# H-API_Sequencer.net
KiCad netlist of a schematic drawn in EAGLE
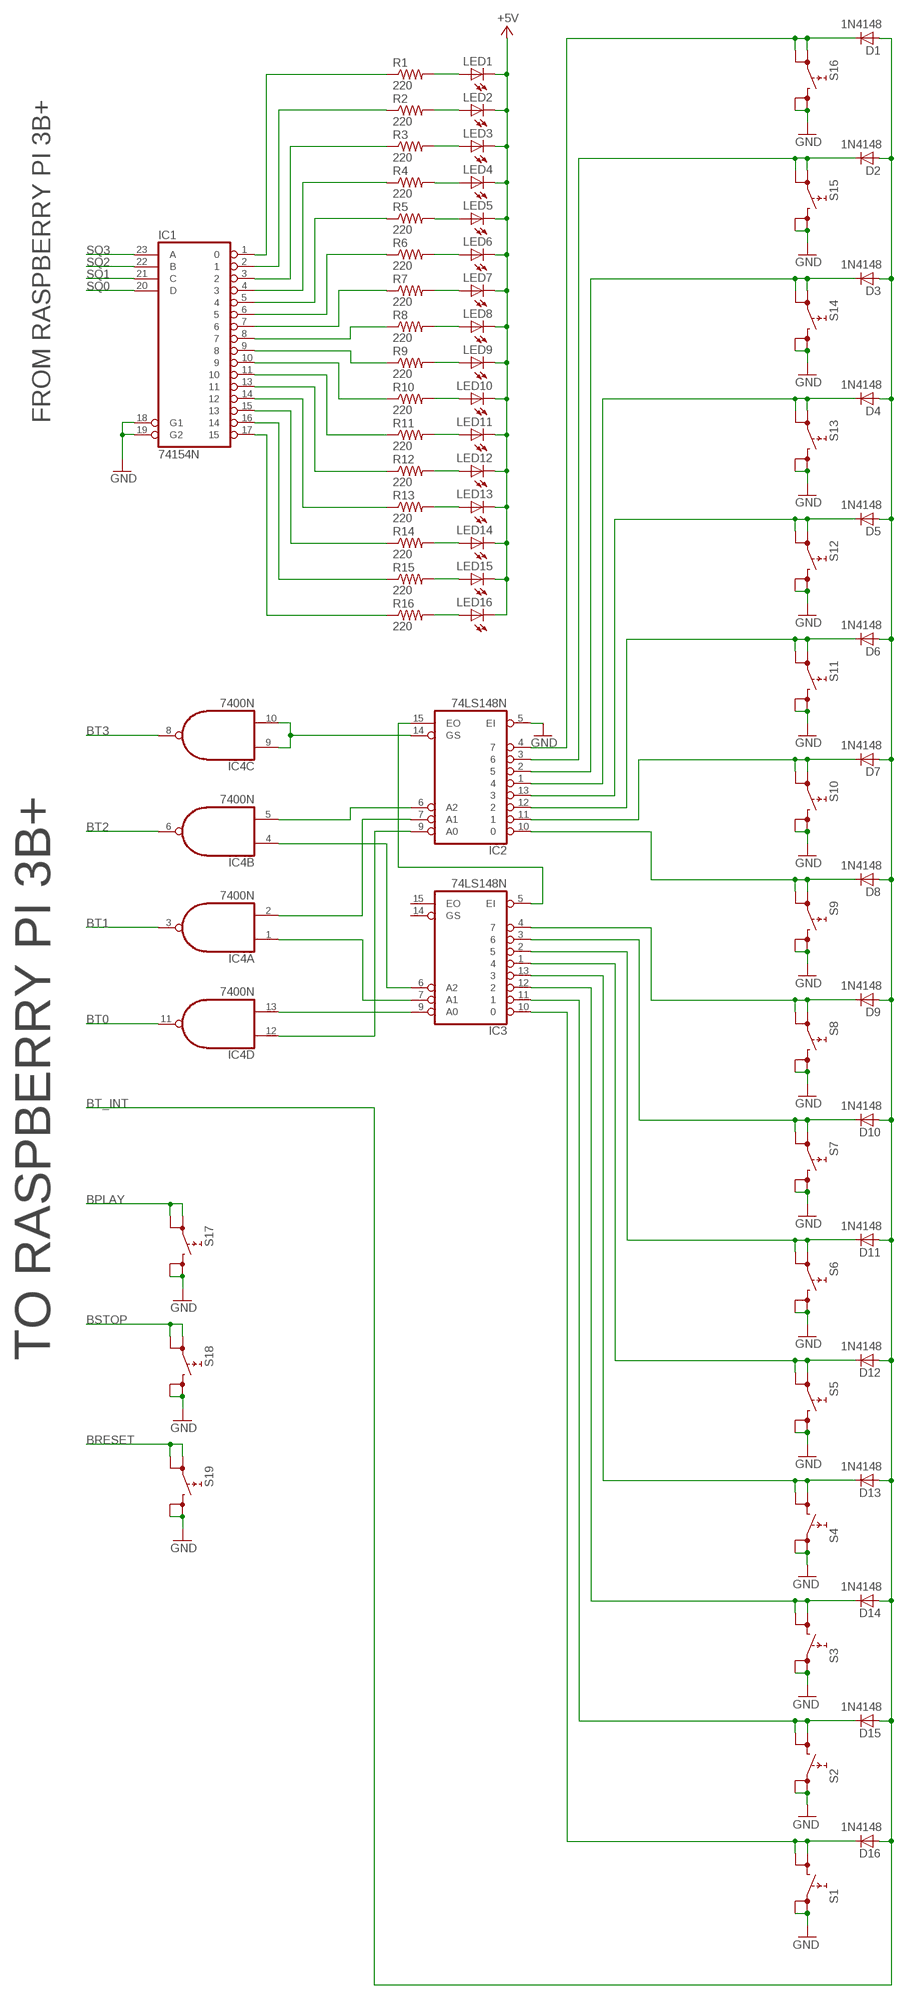
[diagram p0: schematic, sheet 1]

(export (version "E")
  (design (tool "Eeschema 10.0.6"))
  (components
    (comp (ref "IC1")
      (value "74154N")
      (footprint "eagle-import:DIL24-6")
      (libsource (lib "eagle-import") (part "74154N"))
    )
    (comp (ref "IC2")
      (value "74LS148N")
      (footprint "eagle-import:DIL16")
      (libsource (lib "eagle-import") (part "74148NLS"))
    )
    (comp (ref "IC3")
      (value "74LS148N")
      (footprint "eagle-import:DIL16")
      (libsource (lib "eagle-import") (part "74148NLS"))
    )
    (comp (ref "IC4")
      (value "7400N")
      (footprint "eagle-import:DIL14")
      (libsource (lib "eagle-import") (part "7400N"))
    )
    (comp (ref "LED1")
      (value "LED5MM")
      (footprint "eagle-import:LED5MM")
      (libsource (lib "eagle-import") (part "LED5MM"))
    )
    (comp (ref "LED2")
      (value "LED5MM")
      (footprint "eagle-import:LED5MM")
      (libsource (lib "eagle-import") (part "LED5MM"))
    )
    (comp (ref "LED3")
      (value "LED5MM")
      (footprint "eagle-import:LED5MM")
      (libsource (lib "eagle-import") (part "LED5MM"))
    )
    (comp (ref "LED4")
      (value "LED5MM")
      (footprint "eagle-import:LED5MM")
      (libsource (lib "eagle-import") (part "LED5MM"))
    )
    (comp (ref "LED5")
      (value "LED5MM")
      (footprint "eagle-import:LED5MM")
      (libsource (lib "eagle-import") (part "LED5MM"))
    )
    (comp (ref "LED6")
      (value "LED5MM")
      (footprint "eagle-import:LED5MM")
      (libsource (lib "eagle-import") (part "LED5MM"))
    )
    (comp (ref "LED7")
      (value "LED5MM")
      (footprint "eagle-import:LED5MM")
      (libsource (lib "eagle-import") (part "LED5MM"))
    )
    (comp (ref "LED8")
      (value "LED5MM")
      (footprint "eagle-import:LED5MM")
      (libsource (lib "eagle-import") (part "LED5MM"))
    )
    (comp (ref "LED9")
      (value "LED5MM")
      (footprint "eagle-import:LED5MM")
      (libsource (lib "eagle-import") (part "LED5MM"))
    )
    (comp (ref "LED10")
      (value "LED5MM")
      (footprint "eagle-import:LED5MM")
      (libsource (lib "eagle-import") (part "LED5MM"))
    )
    (comp (ref "LED11")
      (value "LED5MM")
      (footprint "eagle-import:LED5MM")
      (libsource (lib "eagle-import") (part "LED5MM"))
    )
    (comp (ref "LED12")
      (value "LED5MM")
      (footprint "eagle-import:LED5MM")
      (libsource (lib "eagle-import") (part "LED5MM"))
    )
    (comp (ref "LED13")
      (value "LED5MM")
      (footprint "eagle-import:LED5MM")
      (libsource (lib "eagle-import") (part "LED5MM"))
    )
    (comp (ref "LED14")
      (value "LED5MM")
      (footprint "eagle-import:LED5MM")
      (libsource (lib "eagle-import") (part "LED5MM"))
    )
    (comp (ref "LED15")
      (value "LED5MM")
      (footprint "eagle-import:LED5MM")
      (libsource (lib "eagle-import") (part "LED5MM"))
    )
    (comp (ref "LED16")
      (value "LED5MM")
      (footprint "eagle-import:LED5MM")
      (libsource (lib "eagle-import") (part "LED5MM"))
    )
    (comp (ref "R1")
      (value "220")
      (footprint "eagle-import:VMTA55")
      (libsource (lib "eagle-import") (part "R-US_VMTA55"))
    )
    (comp (ref "R2")
      (value "220")
      (footprint "eagle-import:VMTA55")
      (libsource (lib "eagle-import") (part "R-US_VMTA55"))
    )
    (comp (ref "R3")
      (value "220")
      (footprint "eagle-import:VMTA55")
      (libsource (lib "eagle-import") (part "R-US_VMTA55"))
    )
    (comp (ref "R4")
      (value "220")
      (footprint "eagle-import:VMTA55")
      (libsource (lib "eagle-import") (part "R-US_VMTA55"))
    )
    (comp (ref "R5")
      (value "220")
      (footprint "eagle-import:VMTA55")
      (libsource (lib "eagle-import") (part "R-US_VMTA55"))
    )
    (comp (ref "R6")
      (value "220")
      (footprint "eagle-import:VMTA55")
      (libsource (lib "eagle-import") (part "R-US_VMTA55"))
    )
    (comp (ref "R7")
      (value "220")
      (footprint "eagle-import:VMTA55")
      (libsource (lib "eagle-import") (part "R-US_VMTA55"))
    )
    (comp (ref "R8")
      (value "220")
      (footprint "eagle-import:VMTA55")
      (libsource (lib "eagle-import") (part "R-US_VMTA55"))
    )
    (comp (ref "R9")
      (value "220")
      (footprint "eagle-import:VMTA55")
      (libsource (lib "eagle-import") (part "R-US_VMTA55"))
    )
    (comp (ref "R10")
      (value "220")
      (footprint "eagle-import:VMTA55")
      (libsource (lib "eagle-import") (part "R-US_VMTA55"))
    )
    (comp (ref "R11")
      (value "220")
      (footprint "eagle-import:VMTA55")
      (libsource (lib "eagle-import") (part "R-US_VMTA55"))
    )
    (comp (ref "R12")
      (value "220")
      (footprint "eagle-import:VMTA55")
      (libsource (lib "eagle-import") (part "R-US_VMTA55"))
    )
    (comp (ref "R13")
      (value "220")
      (footprint "eagle-import:VMTA55")
      (libsource (lib "eagle-import") (part "R-US_VMTA55"))
    )
    (comp (ref "R14")
      (value "220")
      (footprint "eagle-import:VMTA55")
      (libsource (lib "eagle-import") (part "R-US_VMTA55"))
    )
    (comp (ref "R15")
      (value "220")
      (footprint "eagle-import:VMTA55")
      (libsource (lib "eagle-import") (part "R-US_VMTA55"))
    )
    (comp (ref "R16")
      (value "220")
      (footprint "eagle-import:VMTA55")
      (libsource (lib "eagle-import") (part "R-US_VMTA55"))
    )
    (comp (ref "S1")
      (value "REKN")
      (footprint "eagle-import:REKN")
      (libsource (lib "eagle-import") (part "REKN"))
    )
    (comp (ref "S2")
      (value "REKN")
      (footprint "eagle-import:REKN")
      (libsource (lib "eagle-import") (part "REKN"))
    )
    (comp (ref "S3")
      (value "REKN")
      (footprint "eagle-import:REKN")
      (libsource (lib "eagle-import") (part "REKN"))
    )
    (comp (ref "S4")
      (value "REKN")
      (footprint "eagle-import:REKN")
      (libsource (lib "eagle-import") (part "REKN"))
    )
    (comp (ref "S5")
      (value "REKN")
      (footprint "eagle-import:REKN")
      (libsource (lib "eagle-import") (part "REKN"))
    )
    (comp (ref "S6")
      (value "REKN")
      (footprint "eagle-import:REKN")
      (libsource (lib "eagle-import") (part "REKN"))
    )
    (comp (ref "S7")
      (value "REKN")
      (footprint "eagle-import:REKN")
      (libsource (lib "eagle-import") (part "REKN"))
    )
    (comp (ref "S8")
      (value "REKN")
      (footprint "eagle-import:REKN")
      (libsource (lib "eagle-import") (part "REKN"))
    )
    (comp (ref "S9")
      (value "REKN")
      (footprint "eagle-import:REKN")
      (libsource (lib "eagle-import") (part "REKN"))
    )
    (comp (ref "S10")
      (value "REKN")
      (footprint "eagle-import:REKN")
      (libsource (lib "eagle-import") (part "REKN"))
    )
    (comp (ref "S11")
      (value "REKN")
      (footprint "eagle-import:REKN")
      (libsource (lib "eagle-import") (part "REKN"))
    )
    (comp (ref "S12")
      (value "REKN")
      (footprint "eagle-import:REKN")
      (libsource (lib "eagle-import") (part "REKN"))
    )
    (comp (ref "S13")
      (value "REKN")
      (footprint "eagle-import:REKN")
      (libsource (lib "eagle-import") (part "REKN"))
    )
    (comp (ref "S14")
      (value "REKN")
      (footprint "eagle-import:REKN")
      (libsource (lib "eagle-import") (part "REKN"))
    )
    (comp (ref "S15")
      (value "REKN")
      (footprint "eagle-import:REKN")
      (libsource (lib "eagle-import") (part "REKN"))
    )
    (comp (ref "S16")
      (value "REKN")
      (footprint "eagle-import:REKN")
      (libsource (lib "eagle-import") (part "REKN"))
    )
    (comp (ref "S17")
      (value "REKN")
      (footprint "eagle-import:REKN")
      (libsource (lib "eagle-import") (part "REKN"))
    )
    (comp (ref "S18")
      (value "REKN")
      (footprint "eagle-import:REKN")
      (libsource (lib "eagle-import") (part "REKN"))
    )
    (comp (ref "S19")
      (value "REKN")
      (footprint "eagle-import:REKN")
      (libsource (lib "eagle-import") (part "REKN"))
    )
  )
  (nets
    (net (code "1") (name "+5V") (class "Default")
      (node (ref "LED1") (pin "K") (pinfunction "C_K") (pintype "passive"))
      (node (ref "LED10") (pin "K") (pinfunction "C_K") (pintype "passive"))
      (node (ref "LED11") (pin "K") (pinfunction "C_K") (pintype "passive"))
      (node (ref "LED12") (pin "K") (pinfunction "C_K") (pintype "passive"))
      (node (ref "LED13") (pin "K") (pinfunction "C_K") (pintype "passive"))
      (node (ref "LED14") (pin "K") (pinfunction "C_K") (pintype "passive"))
      (node (ref "LED15") (pin "K") (pinfunction "C_K") (pintype "passive"))
      (node (ref "LED16") (pin "K") (pinfunction "C_K") (pintype "passive"))
      (node (ref "LED2") (pin "K") (pinfunction "C_K") (pintype "passive"))
      (node (ref "LED3") (pin "K") (pinfunction "C_K") (pintype "passive"))
      (node (ref "LED4") (pin "K") (pinfunction "C_K") (pintype "passive"))
      (node (ref "LED5") (pin "K") (pinfunction "C_K") (pintype "passive"))
      (node (ref "LED6") (pin "K") (pinfunction "C_K") (pintype "passive"))
      (node (ref "LED7") (pin "K") (pinfunction "C_K") (pintype "passive"))
      (node (ref "LED8") (pin "K") (pinfunction "C_K") (pintype "passive"))
      (node (ref "LED9") (pin "K") (pinfunction "C_K") (pintype "passive"))
    )
    (net (code "2") (name "/BPLAY") (class "Default")
      (node (ref "S17") (pin "0A") (pinfunction "0_0A") (pintype "passive"))
      (node (ref "S17") (pin "0B") (pinfunction "0_0B") (pintype "passive"))
    )
    (net (code "3") (name "/BRESET") (class "Default")
      (node (ref "S19") (pin "0A") (pinfunction "0_0A") (pintype "passive"))
      (node (ref "S19") (pin "0B") (pinfunction "0_0B") (pintype "passive"))
    )
    (net (code "4") (name "/BSTOP") (class "Default")
      (node (ref "S18") (pin "0A") (pinfunction "0_0A") (pintype "passive"))
      (node (ref "S18") (pin "0B") (pinfunction "0_0B") (pintype "passive"))
    )
    (net (code "5") (name "/BT0") (class "Default")
      (node (ref "IC4") (pin "11") (pinfunction "O_11") (pintype "output"))
    )
    (net (code "6") (name "/BT1") (class "Default")
      (node (ref "IC4") (pin "3") (pinfunction "O_3") (pintype "output"))
    )
    (net (code "7") (name "/BT2") (class "Default")
      (node (ref "IC4") (pin "6") (pinfunction "O_6") (pintype "output"))
    )
    (net (code "8") (name "/BT3") (class "Default")
      (node (ref "IC4") (pin "8") (pinfunction "O_8") (pintype "output"))
    )
    (net (code "10") (name "/SQ0") (class "Default")
      (node (ref "IC1") (pin "20") (pinfunction "D_20") (pintype "input"))
    )
    (net (code "11") (name "/SQ1") (class "Default")
      (node (ref "IC1") (pin "21") (pinfunction "C_21") (pintype "input"))
    )
    (net (code "12") (name "/SQ2") (class "Default")
      (node (ref "IC1") (pin "22") (pinfunction "B_22") (pintype "input"))
    )
    (net (code "13") (name "/SQ3") (class "Default")
      (node (ref "IC1") (pin "23") (pinfunction "A_23") (pintype "input"))
    )
    (net (code "14") (name "GND") (class "Default")
      (node (ref "IC1") (pin "18") (pinfunction "G1_18") (pintype "input"))
      (node (ref "IC1") (pin "19") (pinfunction "G2_19") (pintype "input"))
      (node (ref "IC2") (pin "5") (pinfunction "EI_5") (pintype "input"))
      (node (ref "S1") (pin "0A") (pinfunction "0_0A") (pintype "passive"))
      (node (ref "S1") (pin "0B") (pinfunction "0_0B") (pintype "passive"))
      (node (ref "S10") (pin "1A") (pinfunction "1_1A") (pintype "passive"))
      (node (ref "S10") (pin "1B") (pinfunction "1_1B") (pintype "passive"))
      (node (ref "S11") (pin "1A") (pinfunction "1_1A") (pintype "passive"))
      (node (ref "S11") (pin "1B") (pinfunction "1_1B") (pintype "passive"))
      (node (ref "S12") (pin "1A") (pinfunction "1_1A") (pintype "passive"))
      (node (ref "S12") (pin "1B") (pinfunction "1_1B") (pintype "passive"))
      (node (ref "S13") (pin "1A") (pinfunction "1_1A") (pintype "passive"))
      (node (ref "S13") (pin "1B") (pinfunction "1_1B") (pintype "passive"))
      (node (ref "S14") (pin "1A") (pinfunction "1_1A") (pintype "passive"))
      (node (ref "S14") (pin "1B") (pinfunction "1_1B") (pintype "passive"))
      (node (ref "S15") (pin "1A") (pinfunction "1_1A") (pintype "passive"))
      (node (ref "S15") (pin "1B") (pinfunction "1_1B") (pintype "passive"))
      (node (ref "S16") (pin "1A") (pinfunction "1_1A") (pintype "passive"))
      (node (ref "S16") (pin "1B") (pinfunction "1_1B") (pintype "passive"))
      (node (ref "S17") (pin "1A") (pinfunction "1_1A") (pintype "passive"))
      (node (ref "S17") (pin "1B") (pinfunction "1_1B") (pintype "passive"))
      (node (ref "S18") (pin "1A") (pinfunction "1_1A") (pintype "passive"))
      (node (ref "S18") (pin "1B") (pinfunction "1_1B") (pintype "passive"))
      (node (ref "S19") (pin "1A") (pinfunction "1_1A") (pintype "passive"))
      (node (ref "S19") (pin "1B") (pinfunction "1_1B") (pintype "passive"))
      (node (ref "S2") (pin "0A") (pinfunction "0_0A") (pintype "passive"))
      (node (ref "S2") (pin "0B") (pinfunction "0_0B") (pintype "passive"))
      (node (ref "S3") (pin "0A") (pinfunction "0_0A") (pintype "passive"))
      (node (ref "S3") (pin "0B") (pinfunction "0_0B") (pintype "passive"))
      (node (ref "S4") (pin "0A") (pinfunction "0_0A") (pintype "passive"))
      (node (ref "S4") (pin "0B") (pinfunction "0_0B") (pintype "passive"))
      (node (ref "S5") (pin "1A") (pinfunction "1_1A") (pintype "passive"))
      (node (ref "S5") (pin "1B") (pinfunction "1_1B") (pintype "passive"))
      (node (ref "S6") (pin "1A") (pinfunction "1_1A") (pintype "passive"))
      (node (ref "S6") (pin "1B") (pinfunction "1_1B") (pintype "passive"))
      (node (ref "S7") (pin "1A") (pinfunction "1_1A") (pintype "passive"))
      (node (ref "S7") (pin "1B") (pinfunction "1_1B") (pintype "passive"))
      (node (ref "S8") (pin "1A") (pinfunction "1_1A") (pintype "passive"))
      (node (ref "S8") (pin "1B") (pinfunction "1_1B") (pintype "passive"))
      (node (ref "S9") (pin "1A") (pinfunction "1_1A") (pintype "passive"))
      (node (ref "S9") (pin "1B") (pinfunction "1_1B") (pintype "passive"))
    )
    (net (code "15") (name "Net-(IC1A-0)") (class "Default")
      (node (ref "IC1") (pin "1") (pinfunction "0_1") (pintype "output"))
      (node (ref "R1") (pin "1") (pinfunction "1_1") (pintype "passive"))
    )
    (net (code "16") (name "Net-(IC1A-1)") (class "Default")
      (node (ref "IC1") (pin "2") (pinfunction "1_2") (pintype "output"))
      (node (ref "R2") (pin "1") (pinfunction "1_1") (pintype "passive"))
    )
    (net (code "17") (name "Net-(IC1A-2)") (class "Default")
      (node (ref "IC1") (pin "3") (pinfunction "2_3") (pintype "output"))
      (node (ref "R3") (pin "1") (pinfunction "1_1") (pintype "passive"))
    )
    (net (code "18") (name "Net-(IC1A-3)") (class "Default")
      (node (ref "IC1") (pin "4") (pinfunction "3_4") (pintype "output"))
      (node (ref "R4") (pin "1") (pinfunction "1_1") (pintype "passive"))
    )
    (net (code "19") (name "Net-(IC1A-4)") (class "Default")
      (node (ref "IC1") (pin "5") (pinfunction "4_5") (pintype "output"))
      (node (ref "R5") (pin "1") (pinfunction "1_1") (pintype "passive"))
    )
    (net (code "20") (name "Net-(IC1A-5)") (class "Default")
      (node (ref "IC1") (pin "6") (pinfunction "5_6") (pintype "output"))
      (node (ref "R6") (pin "1") (pinfunction "1_1") (pintype "passive"))
    )
    (net (code "21") (name "Net-(IC1A-6)") (class "Default")
      (node (ref "IC1") (pin "7") (pinfunction "6_7") (pintype "output"))
      (node (ref "R7") (pin "1") (pinfunction "1_1") (pintype "passive"))
    )
    (net (code "22") (name "Net-(IC1A-7)") (class "Default")
      (node (ref "IC1") (pin "8") (pinfunction "7_8") (pintype "output"))
      (node (ref "R8") (pin "1") (pinfunction "1_1") (pintype "passive"))
    )
    (net (code "23") (name "Net-(IC1A-8)") (class "Default")
      (node (ref "IC1") (pin "9") (pinfunction "8_9") (pintype "output"))
      (node (ref "R9") (pin "1") (pinfunction "1_1") (pintype "passive"))
    )
    (net (code "24") (name "Net-(IC1A-9)") (class "Default")
      (node (ref "IC1") (pin "10") (pinfunction "9_10") (pintype "output"))
      (node (ref "R10") (pin "1") (pinfunction "1_1") (pintype "passive"))
    )
    (net (code "25") (name "Net-(IC1A-10)") (class "Default")
      (node (ref "IC1") (pin "11") (pinfunction "10_11") (pintype "output"))
      (node (ref "R11") (pin "1") (pinfunction "1_1") (pintype "passive"))
    )
    (net (code "26") (name "Net-(IC1A-11)") (class "Default")
      (node (ref "IC1") (pin "13") (pinfunction "11_13") (pintype "output"))
      (node (ref "R12") (pin "1") (pinfunction "1_1") (pintype "passive"))
    )
    (net (code "27") (name "Net-(IC1A-12)") (class "Default")
      (node (ref "IC1") (pin "14") (pinfunction "12_14") (pintype "output"))
      (node (ref "R13") (pin "1") (pinfunction "1_1") (pintype "passive"))
    )
    (net (code "28") (name "Net-(IC1A-13)") (class "Default")
      (node (ref "IC1") (pin "15") (pinfunction "13_15") (pintype "output"))
      (node (ref "R14") (pin "1") (pinfunction "1_1") (pintype "passive"))
    )
    (net (code "29") (name "Net-(IC1A-14)") (class "Default")
      (node (ref "IC1") (pin "16") (pinfunction "14_16") (pintype "output"))
      (node (ref "R15") (pin "1") (pinfunction "1_1") (pintype "passive"))
    )
    (net (code "30") (name "Net-(IC1A-15)") (class "Default")
      (node (ref "IC1") (pin "17") (pinfunction "15_17") (pintype "output"))
      (node (ref "R16") (pin "1") (pinfunction "1_1") (pintype "passive"))
    )
    (net (code "31") (name "Net-(IC2A-0)") (class "Default")
      (node (ref "IC2") (pin "10") (pinfunction "0_10") (pintype "input"))
      (node (ref "S9") (pin "0A") (pinfunction "0_0A") (pintype "passive"))
      (node (ref "S9") (pin "0B") (pinfunction "0_0B") (pintype "passive"))
    )
    (net (code "32") (name "Net-(IC2A-1)") (class "Default")
      (node (ref "IC2") (pin "11") (pinfunction "1_11") (pintype "input"))
      (node (ref "S10") (pin "0A") (pinfunction "0_0A") (pintype "passive"))
      (node (ref "S10") (pin "0B") (pinfunction "0_0B") (pintype "passive"))
    )
    (net (code "33") (name "Net-(IC2A-2)") (class "Default")
      (node (ref "IC2") (pin "12") (pinfunction "2_12") (pintype "input"))
      (node (ref "S11") (pin "0A") (pinfunction "0_0A") (pintype "passive"))
      (node (ref "S11") (pin "0B") (pinfunction "0_0B") (pintype "passive"))
    )
    (net (code "34") (name "Net-(IC2A-3)") (class "Default")
      (node (ref "IC2") (pin "13") (pinfunction "3_13") (pintype "input"))
      (node (ref "S12") (pin "0A") (pinfunction "0_0A") (pintype "passive"))
      (node (ref "S12") (pin "0B") (pinfunction "0_0B") (pintype "passive"))
    )
    (net (code "35") (name "Net-(IC2A-4)") (class "Default")
      (node (ref "IC2") (pin "1") (pinfunction "4_1") (pintype "input"))
      (node (ref "S13") (pin "0A") (pinfunction "0_0A") (pintype "passive"))
      (node (ref "S13") (pin "0B") (pinfunction "0_0B") (pintype "passive"))
    )
    (net (code "36") (name "Net-(IC2A-5)") (class "Default")
      (node (ref "IC2") (pin "2") (pinfunction "5_2") (pintype "input"))
      (node (ref "S14") (pin "0A") (pinfunction "0_0A") (pintype "passive"))
      (node (ref "S14") (pin "0B") (pinfunction "0_0B") (pintype "passive"))
    )
    (net (code "37") (name "Net-(IC2A-6)") (class "Default")
      (node (ref "IC2") (pin "3") (pinfunction "6_3") (pintype "input"))
      (node (ref "S15") (pin "0A") (pinfunction "0_0A") (pintype "passive"))
      (node (ref "S15") (pin "0B") (pinfunction "0_0B") (pintype "passive"))
    )
    (net (code "38") (name "Net-(IC2A-7)") (class "Default")
      (node (ref "IC2") (pin "4") (pinfunction "7_4") (pintype "input"))
      (node (ref "S16") (pin "0A") (pinfunction "0_0A") (pintype "passive"))
      (node (ref "S16") (pin "0B") (pinfunction "0_0B") (pintype "passive"))
    )
    (net (code "39") (name "Net-(IC2A-A0)") (class "Default")
      (node (ref "IC2") (pin "9") (pinfunction "A0_9") (pintype "output"))
      (node (ref "IC4") (pin "12") (pinfunction "I0_12") (pintype "input"))
    )
    (net (code "40") (name "Net-(IC2A-A1)") (class "Default")
      (node (ref "IC2") (pin "7") (pinfunction "A1_7") (pintype "output"))
      (node (ref "IC4") (pin "2") (pinfunction "I1_2") (pintype "input"))
    )
    (net (code "41") (name "Net-(IC2A-A2)") (class "Default")
      (node (ref "IC2") (pin "6") (pinfunction "A2_6") (pintype "output"))
      (node (ref "IC4") (pin "5") (pinfunction "I1_5") (pintype "input"))
    )
    (net (code "42") (name "Net-(IC2A-EO)") (class "Default")
      (node (ref "IC2") (pin "15") (pinfunction "EO_15") (pintype "output"))
      (node (ref "IC3") (pin "5") (pinfunction "EI_5") (pintype "input"))
    )
    (net (code "43") (name "Net-(IC2A-GS)") (class "Default")
      (node (ref "IC2") (pin "14") (pinfunction "GS_14") (pintype "output"))
      (node (ref "IC4") (pin "10") (pinfunction "I1_10") (pintype "input"))
      (node (ref "IC4") (pin "9") (pinfunction "I0_9") (pintype "input"))
    )
    (net (code "44") (name "Net-(IC3A-0)") (class "Default")
      (node (ref "IC3") (pin "10") (pinfunction "0_10") (pintype "input"))
      (node (ref "S1") (pin "1A") (pinfunction "1_1A") (pintype "passive"))
      (node (ref "S1") (pin "1B") (pinfunction "1_1B") (pintype "passive"))
    )
    (net (code "45") (name "Net-(IC3A-1)") (class "Default")
      (node (ref "IC3") (pin "11") (pinfunction "1_11") (pintype "input"))
      (node (ref "S2") (pin "1A") (pinfunction "1_1A") (pintype "passive"))
      (node (ref "S2") (pin "1B") (pinfunction "1_1B") (pintype "passive"))
    )
    (net (code "46") (name "Net-(IC3A-2)") (class "Default")
      (node (ref "IC3") (pin "12") (pinfunction "2_12") (pintype "input"))
      (node (ref "S3") (pin "1A") (pinfunction "1_1A") (pintype "passive"))
      (node (ref "S3") (pin "1B") (pinfunction "1_1B") (pintype "passive"))
    )
    (net (code "47") (name "Net-(IC3A-3)") (class "Default")
      (node (ref "IC3") (pin "13") (pinfunction "3_13") (pintype "input"))
      (node (ref "S4") (pin "1A") (pinfunction "1_1A") (pintype "passive"))
      (node (ref "S4") (pin "1B") (pinfunction "1_1B") (pintype "passive"))
    )
    (net (code "48") (name "Net-(IC3A-4)") (class "Default")
      (node (ref "IC3") (pin "1") (pinfunction "4_1") (pintype "input"))
      (node (ref "S5") (pin "0A") (pinfunction "0_0A") (pintype "passive"))
      (node (ref "S5") (pin "0B") (pinfunction "0_0B") (pintype "passive"))
    )
    (net (code "49") (name "Net-(IC3A-5)") (class "Default")
      (node (ref "IC3") (pin "2") (pinfunction "5_2") (pintype "input"))
      (node (ref "S6") (pin "0A") (pinfunction "0_0A") (pintype "passive"))
      (node (ref "S6") (pin "0B") (pinfunction "0_0B") (pintype "passive"))
    )
    (net (code "50") (name "Net-(IC3A-6)") (class "Default")
      (node (ref "IC3") (pin "3") (pinfunction "6_3") (pintype "input"))
      (node (ref "S7") (pin "0A") (pinfunction "0_0A") (pintype "passive"))
      (node (ref "S7") (pin "0B") (pinfunction "0_0B") (pintype "passive"))
    )
    (net (code "51") (name "Net-(IC3A-7)") (class "Default")
      (node (ref "IC3") (pin "4") (pinfunction "7_4") (pintype "input"))
      (node (ref "S8") (pin "0A") (pinfunction "0_0A") (pintype "passive"))
      (node (ref "S8") (pin "0B") (pinfunction "0_0B") (pintype "passive"))
    )
    (net (code "52") (name "Net-(IC3A-A0)") (class "Default")
      (node (ref "IC3") (pin "9") (pinfunction "A0_9") (pintype "output"))
      (node (ref "IC4") (pin "13") (pinfunction "I1_13") (pintype "input"))
    )
    (net (code "53") (name "Net-(IC3A-A1)") (class "Default")
      (node (ref "IC3") (pin "7") (pinfunction "A1_7") (pintype "output"))
      (node (ref "IC4") (pin "1") (pinfunction "I0_1") (pintype "input"))
    )
    (net (code "54") (name "Net-(IC3A-A2)") (class "Default")
      (node (ref "IC3") (pin "6") (pinfunction "A2_6") (pintype "output"))
      (node (ref "IC4") (pin "4") (pinfunction "I0_4") (pintype "input"))
    )
    (net (code "55") (name "Net-(LED1-PadA)") (class "Default")
      (node (ref "LED1") (pin "A") (pinfunction "A_A") (pintype "passive"))
      (node (ref "R1") (pin "2") (pinfunction "2_2") (pintype "passive"))
    )
    (net (code "56") (name "Net-(LED2-PadA)") (class "Default")
      (node (ref "LED2") (pin "A") (pinfunction "A_A") (pintype "passive"))
      (node (ref "R2") (pin "2") (pinfunction "2_2") (pintype "passive"))
    )
    (net (code "57") (name "Net-(LED3-PadA)") (class "Default")
      (node (ref "LED3") (pin "A") (pinfunction "A_A") (pintype "passive"))
      (node (ref "R3") (pin "2") (pinfunction "2_2") (pintype "passive"))
    )
    (net (code "58") (name "Net-(LED4-PadA)") (class "Default")
      (node (ref "LED4") (pin "A") (pinfunction "A_A") (pintype "passive"))
      (node (ref "R4") (pin "2") (pinfunction "2_2") (pintype "passive"))
    )
    (net (code "59") (name "Net-(LED5-PadA)") (class "Default")
      (node (ref "LED5") (pin "A") (pinfunction "A_A") (pintype "passive"))
      (node (ref "R5") (pin "2") (pinfunction "2_2") (pintype "passive"))
    )
    (net (code "60") (name "Net-(LED6-PadA)") (class "Default")
      (node (ref "LED6") (pin "A") (pinfunction "A_A") (pintype "passive"))
      (node (ref "R6") (pin "2") (pinfunction "2_2") (pintype "passive"))
    )
    (net (code "61") (name "Net-(LED7-PadA)") (class "Default")
      (node (ref "LED7") (pin "A") (pinfunction "A_A") (pintype "passive"))
      (node (ref "R7") (pin "2") (pinfunction "2_2") (pintype "passive"))
    )
    (net (code "62") (name "Net-(LED8-PadA)") (class "Default")
      (node (ref "LED8") (pin "A") (pinfunction "A_A") (pintype "passive"))
      (node (ref "R8") (pin "2") (pinfunction "2_2") (pintype "passive"))
    )
    (net (code "63") (name "Net-(LED9-PadA)") (class "Default")
      (node (ref "LED9") (pin "A") (pinfunction "A_A") (pintype "passive"))
      (node (ref "R9") (pin "2") (pinfunction "2_2") (pintype "passive"))
    )
    (net (code "64") (name "Net-(LED10-PadA)") (class "Default")
      (node (ref "LED10") (pin "A") (pinfunction "A_A") (pintype "passive"))
      (node (ref "R10") (pin "2") (pinfunction "2_2") (pintype "passive"))
    )
    (net (code "65") (name "Net-(LED11-PadA)") (class "Default")
      (node (ref "LED11") (pin "A") (pinfunction "A_A") (pintype "passive"))
      (node (ref "R11") (pin "2") (pinfunction "2_2") (pintype "passive"))
    )
    (net (code "66") (name "Net-(LED12-PadA)") (class "Default")
      (node (ref "LED12") (pin "A") (pinfunction "A_A") (pintype "passive"))
      (node (ref "R12") (pin "2") (pinfunction "2_2") (pintype "passive"))
    )
    (net (code "67") (name "Net-(LED13-PadA)") (class "Default")
      (node (ref "LED13") (pin "A") (pinfunction "A_A") (pintype "passive"))
      (node (ref "R13") (pin "2") (pinfunction "2_2") (pintype "passive"))
    )
    (net (code "68") (name "Net-(LED14-PadA)") (class "Default")
      (node (ref "LED14") (pin "A") (pinfunction "A_A") (pintype "passive"))
      (node (ref "R14") (pin "2") (pinfunction "2_2") (pintype "passive"))
    )
    (net (code "69") (name "Net-(LED15-PadA)") (class "Default")
      (node (ref "LED15") (pin "A") (pinfunction "A_A") (pintype "passive"))
      (node (ref "R15") (pin "2") (pinfunction "2_2") (pintype "passive"))
    )
    (net (code "70") (name "Net-(LED16-PadA)") (class "Default")
      (node (ref "LED16") (pin "A") (pinfunction "A_A") (pintype "passive"))
      (node (ref "R16") (pin "2") (pinfunction "2_2") (pintype "passive"))
    )
    (net (code "71") (name "unconnected-(IC3A-EO-Pad15)") (class "Default")
      (node (ref "IC3") (pin "15") (pinfunction "EO_15") (pintype "output"))
    )
    (net (code "72") (name "unconnected-(IC3A-GS-Pad14)") (class "Default")
      (node (ref "IC3") (pin "14") (pinfunction "GS_14") (pintype "output"))
    )
  )
)
